# pca10040_sheet5_power_supply.net
KiCad netlist of a schematic drawn in Altium Designer
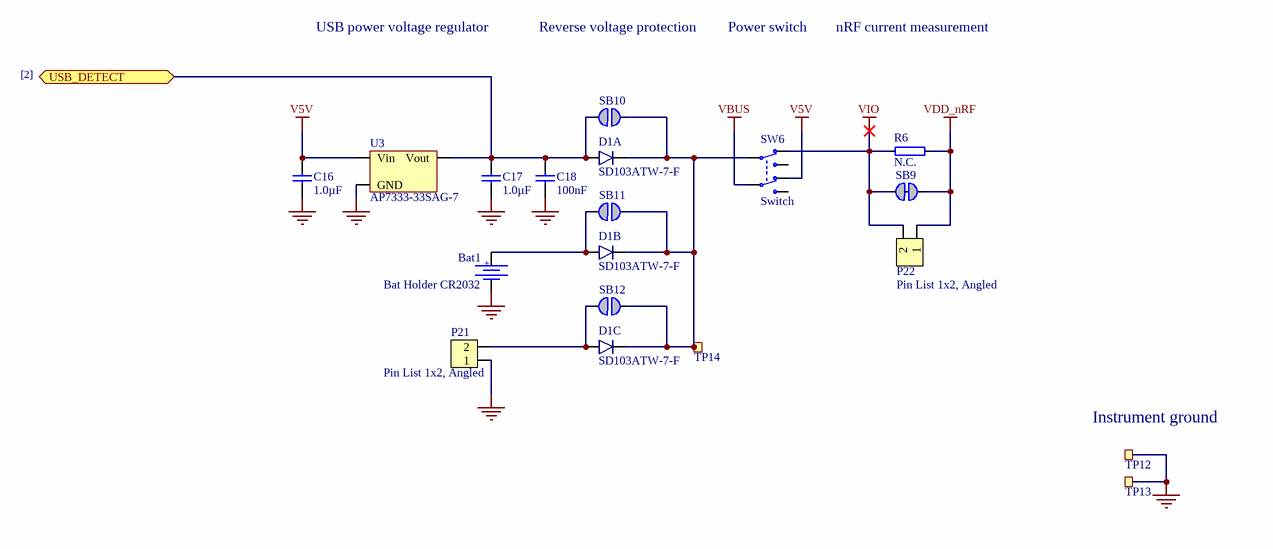
[diagram p0: pca10040_sheet5_power_supply.SchDoc]

(export (version "E")
  (design (tool "Eeschema 10.0.6"))
  (components
    (comp (ref "Bat1")
      (value "Bat Holder CR2032")
      (footprint "CR2032_HOLDER_SMD")
      (description "Bat Holder CR2032 SMD")
      (fields
        (field (name "MANUFACTURER") "Keystone")
        (field (name "MANUFACTURER PART NUMBER") "3002")
        (field (name "PUBLISHER") "Nordic Semiconductor")
      )
      (libsource (lib "Nordic Passive DB") (part "Battery"))
    )
    (comp (ref "C16")
      (value "1.0µF")
      (footprint "CAPC1608X06L")
      (description "Capacitor, X7R, ±10%")
      (fields (field (name "PART NUMBER") "C0603-1µ0") (field (name "PUBLISHER") "Nordic Semiconductor"))
      (libsource (lib "Nordic Passive DB") (part "CAP"))
    )
    (comp (ref "C17")
      (value "1.0µF")
      (footprint "CAPC1608X06L")
      (description "Capacitor, X7R, ±10%")
      (fields (field (name "PART NUMBER") "C0603-1µ0") (field (name "PUBLISHER") "Nordic Semiconductor"))
      (libsource (lib "Nordic Passive DB") (part "CAP"))
    )
    (comp (ref "C18")
      (value "100nF")
      (footprint "CAPC1005X04L")
      (description "Capacitor, X7R, ±10%")
      (fields (field (name "PART NUMBER") "C0402-100n") (field (name "PUBLISHER") "Nordic Semiconductor"))
      (libsource (lib "Nordic Passive DB") (part "CAP"))
    )
    (comp (ref "D1")
      (value "SD103ATW-7-F")
      (footprint "SOT-363")
      (description "Surface Mount Schottky Barrier Diode Array")
      (fields
        (field (name "MANUFACTURER") "Diodes Incorporated")
        (field (name "2ND SOURCE PART NUMBER") "177-3507")
        (field (name "PUBLISHER") "Nordic Semiconductor")
      )
      (libsource (lib "Nordic Discrete DB") (part "D{colon}DIODE_3_IND"))
    )
    (comp (ref "P21")
      (value "Pin List 1x2, Angled")
      (footprint "LIST_ANG_1x2-SMD-2.54MM")
      (description "Pin List 1x2, 2.54mm (100mil), Right Angled, SMD")
      (fields
        (field (name "PART NUMBER") "Pin List Ang 1x2 SMD, 2.54mm")
        (field (name "2ND SOURCE PART NUMBER") "S1113E-02-ND")
        (field (name "PUBLISHER") "Nordic Semiconductor")
      )
      (libsource (lib "Nordic Passive DB") (part "CONN-2"))
    )
    (comp (ref "P22")
      (value "Pin List 1x2, Angled")
      (footprint "LIST_ANG_1x2-SMD-2.54MM")
      (description "Pin List 1x2, 2.54mm (100mil), Right Angled, SMD")
      (fields
        (field (name "PART NUMBER") "Pin List Ang 1x2 SMD, 2.54mm")
        (field (name "2ND SOURCE PART NUMBER") "S1113E-02-ND")
        (field (name "PUBLISHER") "Nordic Semiconductor")
      )
      (libsource (lib "") (part "CONN-2_1"))
    )
    (comp (ref "R6")
      (value "N.C.")
      (footprint "RESC1005X04L")
      (description "Not mounted")
      (fields (field (name "PART NUMBER") "R0402-N.C.") (field (name "PUBLISHER") "Nordic Semiconductor"))
      (libsource (lib "Nordic Passive DB") (part "RES_1"))
    )
    (comp (ref "SB9")
      (value "Solderbridge")
      (footprint "Solderbridge_Shorted")
      (description "Shorted Solderbridge")
      (fields
        (field (name "PART NUMBER") "Solderbridge Shorted")
        (field (name "PUBLISHER") "Nordic Semiconductor")
      )
      (libsource (lib "Nordic Passive DB") (part "SOLDERBRIDGE_SHORTED"))
    )
    (comp (ref "SB10")
      (value "Solderbridge")
      (footprint "Solderbridge")
      (fields (field (name "PUBLISHER") "Nordic Semiconductor"))
      (libsource (lib "Nordic Passive DB") (part "SOLDERBRIDGE"))
    )
    (comp (ref "SB11")
      (value "Solderbridge")
      (footprint "Solderbridge")
      (fields (field (name "PUBLISHER") "Nordic Semiconductor"))
      (libsource (lib "Nordic Passive DB") (part "SOLDERBRIDGE"))
    )
    (comp (ref "SB12")
      (value "Solderbridge")
      (footprint "Solderbridge")
      (fields (field (name "PUBLISHER") "Nordic Semiconductor"))
      (libsource (lib "Nordic Passive DB") (part "SOLDERBRIDGE"))
    )
    (comp (ref "SW6")
      (value "Switch")
      (footprint "JS202011SCQN")
      (description "SMD slide Switch (ON-ON)")
      (fields
        (field (name "PART NUMBER") "JS202011SCQN")
        (field (name "MANUFACTURER") "C&K Components")
        (field (name "PUBLISHER") "Nordic Semiconductor")
      )
      (libsource (lib "Nordic Discrete DB") (part "SW-DPDT"))
    )
    (comp (ref "TP12")
      (value "TP")
      (footprint "TESTPAD-TH")
      (description "Testpoint, through hole")
      (fields (field (name "PART NUMBER") "Testpoint TH") (field (name "PUBLISHER") "Nordic Semiconductor"))
      (libsource (lib "") (part "TESTPAD_1"))
    )
    (comp (ref "TP13")
      (value "TP")
      (footprint "TESTPAD-TH")
      (description "Testpoint, through hole")
      (fields (field (name "PART NUMBER") "Testpoint TH") (field (name "PUBLISHER") "Nordic Semiconductor"))
      (libsource (lib "") (part "TESTPAD_1"))
    )
    (comp (ref "TP14")
      (value "Ø1.0mm,SMD")
      (footprint "TP_SMD_Ø1.0mm")
      (description "1.0mm circular SMD testpad")
      (fields
        (field (name "PART NUMBER") "TP_SMD_Ø1.0MM")
        (field (name "MANUFACTURER") "Nordic Semiconductor")
        (field (name "PUBLISHER") "Nordic Semiconductor")
      )
      (libsource (lib "Nordic Passive DB") (part "TESTPAD"))
    )
    (comp (ref "U3")
      (value "AP7333-33SAG-7")
      (footprint "SOT-23A")
      (description "300mA, Low Quiescent Current, Fast Transient Low Dropout Linear Regulator")
      (fields
        (field (name "MANUFACTURER") "Diodes Incorporated")
        (field (name "PUBLISHER") "Nordic Semiconductor")
      )
      (libsource (lib "Nordic Active DB") (part "AP7333-XXSAG"))
    )
  )
  (nets
    (net (code "1") (name "/USB_DETECT") (class "Default")
      (node (ref "C17") (pin "2") (pinfunction "2_2") (pintype "passive"))
      (node (ref "C18") (pin "2") (pinfunction "2_2") (pintype "passive"))
      (node (ref "D1") (pin "6") (pinfunction "A1_6") (pintype "passive"))
      (node (ref "SB10") (pin "2") (pinfunction "1_2") (pintype "passive"))
      (node (ref "U3") (pin "2") (pinfunction "Vout_2") (pintype "passive"))
    )
    (net (code "2") (name "GND") (class "Default")
      (node (ref "Bat1") (pin "2") (pintype "passive"))
      (node (ref "C16") (pin "1") (pinfunction "1_1") (pintype "passive"))
      (node (ref "C17") (pin "1") (pinfunction "1_1") (pintype "passive"))
      (node (ref "C18") (pin "1") (pinfunction "1_1") (pintype "passive"))
      (node (ref "P21") (pin "1") (pinfunction "1_1") (pintype "passive"))
      (node (ref "TP12") (pin "1") (pinfunction "1_1") (pintype "passive"))
      (node (ref "TP13") (pin "1") (pinfunction "1_1") (pintype "passive"))
      (node (ref "U3") (pin "3") (pinfunction "GND_3") (pintype "passive"))
    )
    (net (code "3") (name "Net-(D1A-C1)") (class "Default")
      (node (ref "D1") (pin "1") (pinfunction "C1_1") (pintype "passive"))
      (node (ref "D1") (pin "2") (pinfunction "C2_2") (pintype "passive"))
      (node (ref "D1") (pin "3") (pinfunction "C3_3") (pintype "passive"))
      (node (ref "SB10") (pin "1") (pinfunction "0_1") (pintype "passive"))
      (node (ref "SB11") (pin "1") (pinfunction "0_1") (pintype "passive"))
      (node (ref "SB12") (pin "1") (pinfunction "0_1") (pintype "passive"))
      (node (ref "SW6") (pin "2") (pinfunction "COM-1_2") (pintype "passive"))
      (node (ref "TP14") (pin "1") (pinfunction "1_1") (pintype "passive"))
    )
    (net (code "4") (name "Net-(D1B-A2)") (class "Default")
      (node (ref "Bat1") (pin "1") (pintype "passive"))
      (node (ref "D1") (pin "5") (pinfunction "A2_5") (pintype "passive"))
      (node (ref "SB11") (pin "2") (pinfunction "1_2") (pintype "passive"))
    )
    (net (code "5") (name "Net-(D1C-A3)") (class "Default")
      (node (ref "D1") (pin "4") (pinfunction "A3_4") (pintype "passive"))
      (node (ref "P21") (pin "2") (pinfunction "2_2") (pintype "passive"))
      (node (ref "SB12") (pin "2") (pinfunction "1_2") (pintype "passive"))
    )
    (net (code "6") (name "V5V") (class "Default")
      (node (ref "C16") (pin "2") (pinfunction "2_2") (pintype "passive"))
      (node (ref "SW6") (pin "6") (pinfunction "N.C-2_6") (pintype "passive"))
      (node (ref "U3") (pin "1") (pinfunction "Vin_1") (pintype "passive"))
    )
    (net (code "7") (name "VBUS") (class "Default")
      (node (ref "SW6") (pin "5") (pinfunction "COM-2_5") (pintype "passive"))
    )
    (net (code "8") (name "VDD_nRF") (class "Default")
      (node (ref "P22") (pin "1") (pinfunction "1_1") (pintype "passive"))
      (node (ref "R6") (pin "2") (pinfunction "2_2") (pintype "passive"))
      (node (ref "SB9") (pin "1") (pinfunction "0_1") (pintype "passive"))
    )
    (net (code "9") (name "VIO") (class "Default")
      (node (ref "P22") (pin "2") (pinfunction "2_2") (pintype "passive"))
      (node (ref "R6") (pin "1") (pinfunction "1_1") (pintype "passive"))
      (node (ref "SB9") (pin "2") (pinfunction "1_2") (pintype "passive"))
      (node (ref "SW6") (pin "3") (pinfunction "N.C-1_3") (pintype "passive"))
    )
    (net (code "10") (name "unconnected-(SW6-N.O-1-Pad1)") (class "Default")
      (node (ref "SW6") (pin "1") (pinfunction "N.O-1_1") (pintype "passive"))
    )
    (net (code "11") (name "unconnected-(SW6-N.O-2-Pad4)") (class "Default")
      (node (ref "SW6") (pin "4") (pinfunction "N.O-2_4") (pintype "passive"))
    )
  )
)
